# OTP2.net
KiCad netlist of a schematic drawn in Altium Designer
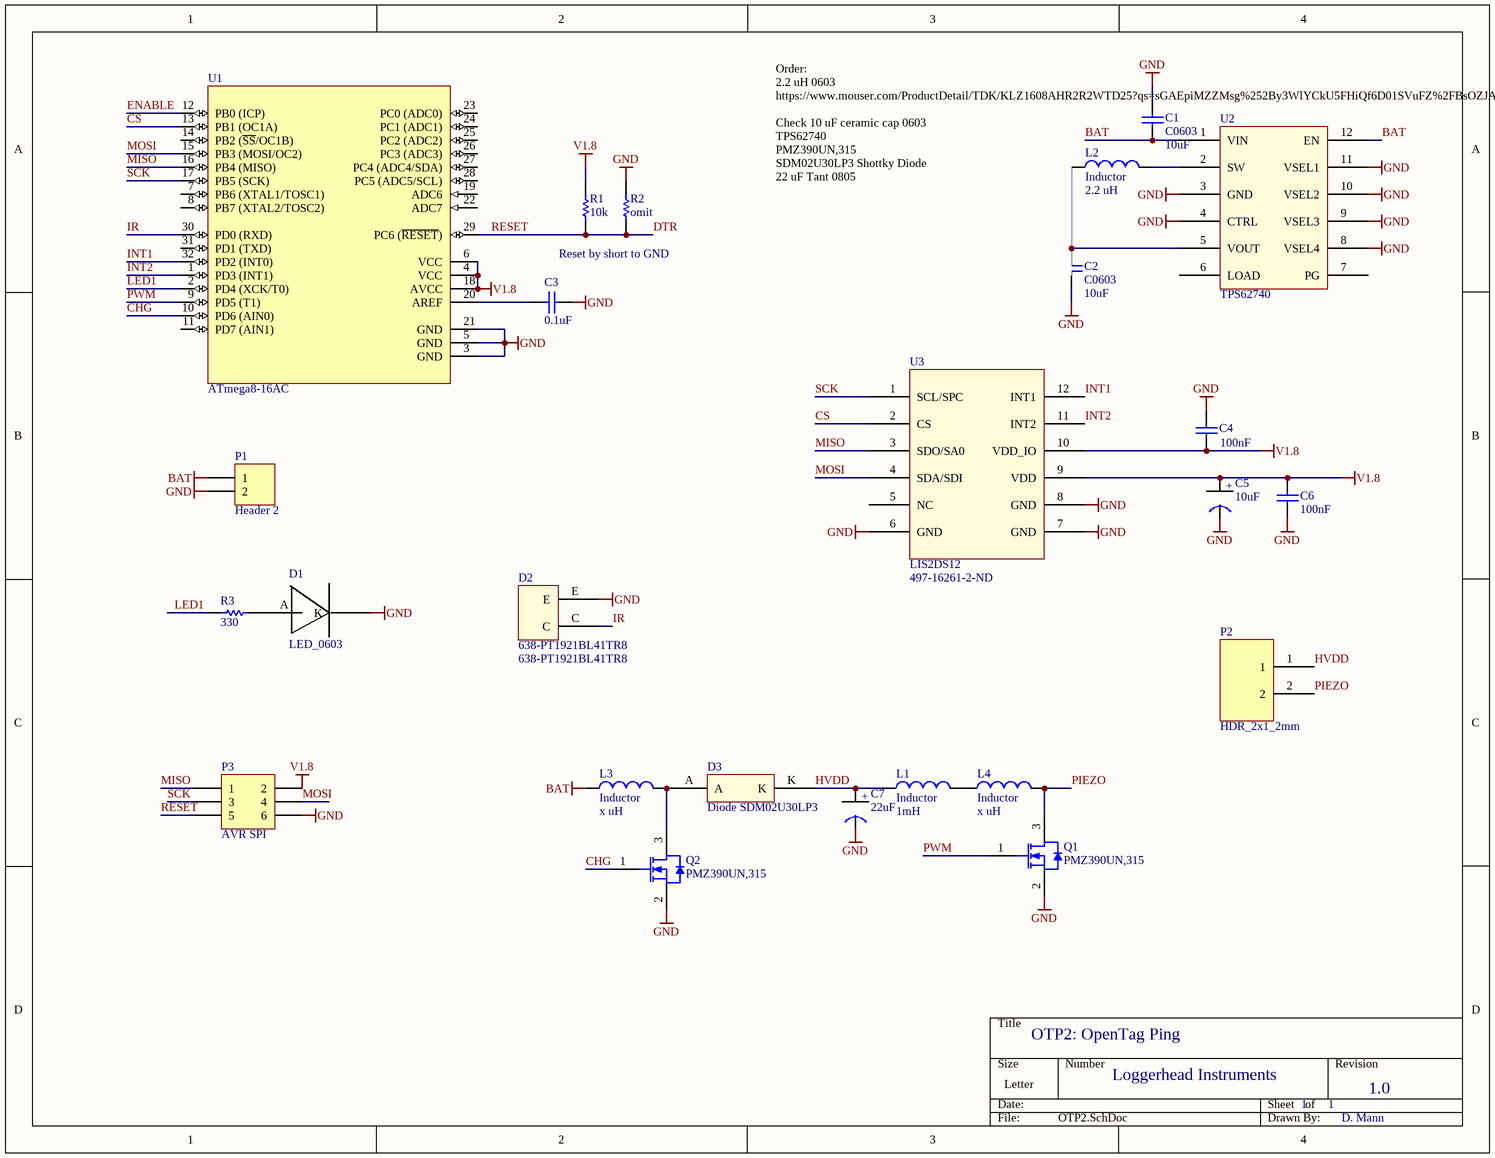
[diagram p0: OTP2.SchDoc]

(export (version "E")
  (design (tool "Eeschema 10.0.6"))
  (components
    (comp (ref "C1")
      (value "C0603")
      (footprint "0603")
      (description "Ceramic Chip Capacitor - Standard")
      (fields (field (name "ALTIUM_VALUE") "10uF") (field (name "PUBLISHER") "Altium Limited"))
      (libsource (lib "KEMET Chip Capacitor") (part "C0603"))
    )
    (comp (ref "C2")
      (value "C0603")
      (footprint "0603")
      (description "Ceramic Chip Capacitor - Standard")
      (fields (field (name "ALTIUM_VALUE") "10uF") (field (name "PUBLISHER") "Altium Limited"))
      (libsource (lib "KEMET Chip Capacitor") (part "C0603"))
    )
    (comp (ref "C3")
      (value "0.1uF")
      (footprint "0402")
      (description "Ceramic Chip Capacitor - Standard")
      (fields (field (name "PUBLISHER") "Altium Limited"))
      (libsource (lib "KEMET Chip Capacitor") (part "C0402"))
    )
    (comp (ref "C4")
      (value "100nF")
      (footprint "0402")
      (description "Ceramic Chip Capacitor - Standard")
      (fields (field (name "PUBLISHER") "Altium Limited"))
      (libsource (lib "KEMET Chip Capacitor") (part "C0402"))
    )
    (comp (ref "C5") (value "10uF") (footprint "Tant0805") (libsource (lib "Loggerhead") (part "Tant0805")))
    (comp (ref "C6")
      (value "100nF")
      (footprint "0402")
      (description "Ceramic Chip Capacitor - Standard")
      (fields (field (name "PUBLISHER") "Altium Limited"))
      (libsource (lib "KEMET Chip Capacitor") (part "C0402"))
    )
    (comp (ref "C7") (value "22uF") (footprint "Tant0805") (libsource (lib "Loggerhead") (part "Tant0805")))
    (comp (ref "D1")
      (value "LED_0603")
      (footprint "Diode0603")
      (libsource (lib "Loggerhead") (part "LED_0603"))
    )
    (comp (ref "D2")
      (value "638-PT1921BL41TR8")
      (footprint "Phototransistor")
      (description "Phototransistor")
      (fields (field (name "SUPPLIER PART NUMBER 1") "638-PT1921BL41TR8"))
      (libsource (lib "Loggerhead") (part "Phototransistor"))
    )
    (comp (ref "D3")
      (value "Diode SDM02U30LP3")
      (footprint "Diode SDM02U30LP3-7B")
      (description "SDM02U30LP3")
      (libsource (lib "Loggerhead") (part "Diode SDM02U30LP3"))
    )
    (comp (ref "L1")
      (value "Inductor")
      (footprint "INDC3216")
      (fields (field (name "ALTIUM_VALUE") "1mH") (field (name "PUBLISHER") "Altium Limited"))
      (libsource (lib "Miscellaneous Devices") (part "Inductor"))
    )
    (comp (ref "L2")
      (value "Inductor")
      (footprint "0603")
      (fields (field (name "ALTIUM_VALUE") "2.2 uH") (field (name "PUBLISHER") "Altium Limited"))
      (libsource (lib "Miscellaneous Devices") (part "Inductor"))
    )
    (comp (ref "L3")
      (value "Inductor")
      (footprint "0603")
      (fields (field (name "ALTIUM_VALUE") "x uH") (field (name "PUBLISHER") "Altium Limited"))
      (libsource (lib "Miscellaneous Devices") (part "Inductor"))
    )
    (comp (ref "L4")
      (value "Inductor")
      (footprint "0603")
      (fields (field (name "ALTIUM_VALUE") "x uH") (field (name "PUBLISHER") "Altium Limited"))
      (libsource (lib "Miscellaneous Devices") (part "Inductor"))
    )
    (comp (ref "P1")
      (value "Header 2")
      (footprint "HDR1X2")
      (description "Header, 2-Pin")
      (fields (field (name "PUBLISHER") "Altium Limited"))
      (libsource (lib "Miscellaneous Connectors") (part "Header 2"))
    )
    (comp (ref "P2")
      (value "HDR_2x1_2mm")
      (footprint "HDR_2x1_2mm")
      (libsource (lib "Loggerhead") (part "HDR_2x1_2mm"))
    )
    (comp (ref "P3")
      (value "AVR SPI")
      (footprint "HDR2X3")
      (description "Header, 3-Pin, Dual row")
      (fields (field (name "PUBLISHER") "Altium Limited"))
      (libsource (lib "Miscellaneous Connectors") (part "Header 3X2"))
    )
    (comp (ref "Q1")
      (value "PMZ390UN,315")
      (footprint "NXP-SOT883_N")
      (description "N-Channel TrenchMOS Standard Level FET, 30 V, 1.78 A, 3-Pin SOT883, Tape and Reel")
      (fields (field (name "MANUFACTURER") "NXP Semiconductors"))
      (libsource (lib "NXP Semiconductors Standard MOSFETs") (part "PMZ390UN,315"))
    )
    (comp (ref "Q2")
      (value "PMZ390UN,315")
      (footprint "NXP-SOT883_N")
      (description "N-Channel TrenchMOS Standard Level FET, 30 V, 1.78 A, 3-Pin SOT883, Tape and Reel")
      (fields (field (name "MANUFACTURER") "NXP Semiconductors"))
      (libsource (lib "NXP Semiconductors Standard MOSFETs") (part "PMZ390UN,315"))
    )
    (comp (ref "R1")
      (value "10k")
      (footprint "3-0603")
      (fields (field (name "PUBLISHER") "Altium Limited"))
      (libsource (lib "Panasonic Resistor") (part "ERJ3RK"))
    )
    (comp (ref "R2")
      (value "omit")
      (footprint "3-0603")
      (fields (field (name "PUBLISHER") "Altium Limited"))
      (libsource (lib "Panasonic Resistor") (part "ERJ3RK"))
    )
    (comp (ref "R3")
      (value "330")
      (footprint "3-0603")
      (fields (field (name "PUBLISHER") "Altium Limited"))
      (libsource (lib "Panasonic Resistor") (part "ERJ3RK"))
    )
    (comp (ref "U1")
      (value "ATmega8-16AC")
      (footprint "32M1-A_M")
      (description "8-Bit AVR Microcontroller with 8K Bytes of In-System Programmable Flash Memory")
      (fields (field (name "PUBLISHER") "Altium Limited"))
      (libsource (lib "Atmel Microcontroller 8-Bit AVR") (part "ATmega8-16AC"))
    )
    (comp (ref "U2")
      (value "TPS62740")
      (footprint "TPS6274x")
      (libsource (lib "Loggerhead") (part "TPS6274x"))
    )
    (comp (ref "U3")
      (value "LIS2DS12")
      (footprint "LGA-12")
      (fields (field (name "SUPPLIER PART NUMBER 1") "497-16261-2-ND"))
      (libsource (lib "Loggerhead") (part "LIS2DS12"))
    )
  )
  (nets
    (net (code "1") (name "/CHG") (class "Default")
      (node (ref "Q2") (pin "1") (pinfunction "G_1") (pintype "passive"))
      (node (ref "U1") (pin "10") (pinfunction "PD6_(AIN0)_10") (pintype "bidirectional"))
    )
    (net (code "2") (name "/CS") (class "Default")
      (node (ref "U1") (pin "13") (pinfunction "PB1_(OC1A)_13") (pintype "bidirectional"))
      (node (ref "U3") (pin "2") (pinfunction "CS_2") (pintype "passive"))
    )
    (net (code "3") (name "/DTR") (class "Default")
      (node (ref "P3") (pin "5") (pinfunction "5_5") (pintype "passive"))
      (node (ref "R1") (pin "1") (pinfunction "1_1") (pintype "passive"))
      (node (ref "R2") (pin "1") (pinfunction "1_1") (pintype "passive"))
      (node (ref "U1") (pin "29") (pinfunction "PC6_(~{RESET})_29") (pintype "bidirectional"))
    )
    (net (code "4") (name "/ENABLE") (class "Default")
      (node (ref "U1") (pin "12") (pinfunction "PB0_(ICP)_12") (pintype "bidirectional"))
    )
    (net (code "5") (name "/HVDD") (class "Default")
      (node (ref "C7") (pin "2") (pinfunction "+_2") (pintype "passive"))
      (node (ref "D3") (pin "K") (pinfunction "K_K") (pintype "passive"))
      (node (ref "L1") (pin "1") (pinfunction "1_1") (pintype "passive"))
      (node (ref "P2") (pin "1") (pinfunction "1_1") (pintype "passive"))
    )
    (net (code "6") (name "/INT1") (class "Default")
      (node (ref "U1") (pin "32") (pinfunction "PD2_(INT0)_32") (pintype "bidirectional"))
      (node (ref "U3") (pin "12") (pinfunction "INT1_12") (pintype "passive"))
    )
    (net (code "7") (name "/INT2") (class "Default")
      (node (ref "U1") (pin "1") (pinfunction "PD3_(INT1)_1") (pintype "bidirectional"))
      (node (ref "U3") (pin "11") (pinfunction "INT2_11") (pintype "passive"))
    )
    (net (code "8") (name "/IR") (class "Default")
      (node (ref "D2") (pin "C") (pinfunction "C_C") (pintype "passive"))
      (node (ref "U1") (pin "30") (pinfunction "PD0_(RXD)_30") (pintype "bidirectional"))
    )
    (net (code "9") (name "/LED1") (class "Default")
      (node (ref "R3") (pin "1") (pinfunction "1_1") (pintype "passive"))
      (node (ref "U1") (pin "2") (pinfunction "PD4_(XCK/T0)_2") (pintype "bidirectional"))
    )
    (net (code "10") (name "/MISO") (class "Default")
      (node (ref "P3") (pin "1") (pinfunction "1_1") (pintype "passive"))
      (node (ref "U1") (pin "16") (pinfunction "PB4_(MISO)_16") (pintype "bidirectional"))
      (node (ref "U3") (pin "3") (pinfunction "SDO/SA0_3") (pintype "passive"))
    )
    (net (code "11") (name "/MOSI") (class "Default")
      (node (ref "P3") (pin "4") (pinfunction "4_4") (pintype "passive"))
      (node (ref "U1") (pin "15") (pinfunction "PB3_(MOSI/OC2)_15") (pintype "bidirectional"))
      (node (ref "U3") (pin "4") (pinfunction "SDA/SDI_4") (pintype "passive"))
    )
    (net (code "12") (name "/PIEZO") (class "Default")
      (node (ref "L4") (pin "2") (pinfunction "2_2") (pintype "passive"))
      (node (ref "P2") (pin "2") (pinfunction "2_2") (pintype "passive"))
      (node (ref "Q1") (pin "3") (pinfunction "D_3") (pintype "passive"))
    )
    (net (code "13") (name "/PWM") (class "Default")
      (node (ref "Q1") (pin "1") (pinfunction "G_1") (pintype "passive"))
      (node (ref "U1") (pin "9") (pinfunction "PD5_(T1)_9") (pintype "bidirectional"))
    )
    (net (code "14") (name "/SCK") (class "Default")
      (node (ref "P3") (pin "3") (pinfunction "3_3") (pintype "passive"))
      (node (ref "U1") (pin "17") (pinfunction "PB5_(SCK)_17") (pintype "bidirectional"))
      (node (ref "U3") (pin "1") (pinfunction "SCL/SPC_1") (pintype "passive"))
    )
    (net (code "15") (name "BAT") (class "Default")
      (node (ref "C1") (pin "1") (pinfunction "1_1") (pintype "passive"))
      (node (ref "L3") (pin "1") (pinfunction "1_1") (pintype "passive"))
      (node (ref "P1") (pin "1") (pinfunction "1_1") (pintype "passive"))
      (node (ref "U2") (pin "1") (pinfunction "VIN_1") (pintype "passive"))
      (node (ref "U2") (pin "12") (pinfunction "EN_12") (pintype "passive"))
    )
    (net (code "16") (name "GND") (class "Default")
      (node (ref "C1") (pin "2") (pinfunction "2_2") (pintype "passive"))
      (node (ref "C2") (pin "1") (pinfunction "1_1") (pintype "passive"))
      (node (ref "C3") (pin "2") (pinfunction "2_2") (pintype "passive"))
      (node (ref "C4") (pin "2") (pinfunction "2_2") (pintype "passive"))
      (node (ref "C5") (pin "1") (pinfunction "GND_1") (pintype "passive"))
      (node (ref "C6") (pin "2") (pinfunction "2_2") (pintype "passive"))
      (node (ref "C7") (pin "1") (pinfunction "GND_1") (pintype "passive"))
      (node (ref "D1") (pin "K") (pinfunction "K_K") (pintype "passive"))
      (node (ref "D2") (pin "E") (pinfunction "E_E") (pintype "passive"))
      (node (ref "P1") (pin "2") (pinfunction "2_2") (pintype "passive"))
      (node (ref "P3") (pin "6") (pinfunction "6_6") (pintype "passive"))
      (node (ref "Q1") (pin "2") (pinfunction "S_2") (pintype "passive"))
      (node (ref "Q2") (pin "2") (pinfunction "S_2") (pintype "passive"))
      (node (ref "R2") (pin "2") (pinfunction "2_2") (pintype "passive"))
      (node (ref "U1") (pin "21") (pinfunction "GND_21") (pintype "power_in"))
      (node (ref "U1") (pin "3") (pinfunction "GND_3") (pintype "power_in"))
      (node (ref "U1") (pin "5") (pinfunction "GND_5") (pintype "power_in"))
      (node (ref "U2") (pin "10") (pinfunction "VSEL2_10") (pintype "passive"))
      (node (ref "U2") (pin "11") (pinfunction "VSEL1_11") (pintype "passive"))
      (node (ref "U2") (pin "3") (pinfunction "GND_3") (pintype "passive"))
      (node (ref "U2") (pin "4") (pinfunction "CTRL_4") (pintype "passive"))
      (node (ref "U2") (pin "8") (pinfunction "VSEL4_8") (pintype "passive"))
      (node (ref "U2") (pin "9") (pinfunction "VSEL3_9") (pintype "passive"))
      (node (ref "U3") (pin "6") (pinfunction "GND_6") (pintype "passive"))
      (node (ref "U3") (pin "7") (pinfunction "GND_7") (pintype "passive"))
      (node (ref "U3") (pin "8") (pinfunction "GND_8") (pintype "passive"))
    )
    (net (code "17") (name "Net-(D1-PadA)") (class "Default")
      (node (ref "D1") (pin "A") (pinfunction "A_A") (pintype "passive"))
      (node (ref "R3") (pin "2") (pinfunction "2_2") (pintype "passive"))
    )
    (net (code "18") (name "Net-(L1-Pad2)") (class "Default")
      (node (ref "L1") (pin "2") (pinfunction "2_2") (pintype "passive"))
      (node (ref "L4") (pin "1") (pinfunction "1_1") (pintype "passive"))
    )
    (net (code "19") (name "Net-(Q2-D)") (class "Default")
      (node (ref "D3") (pin "A") (pinfunction "A_A") (pintype "passive"))
      (node (ref "L3") (pin "2") (pinfunction "2_2") (pintype "passive"))
      (node (ref "Q2") (pin "3") (pinfunction "D_3") (pintype "passive"))
    )
    (net (code "20") (name "Net-(U1-AREF)") (class "Default")
      (node (ref "C3") (pin "1") (pinfunction "1_1") (pintype "passive"))
      (node (ref "U1") (pin "20") (pinfunction "AREF_20") (pintype "passive"))
    )
    (net (code "21") (name "Net-(U2-SW)") (class "Default")
      (node (ref "L2") (pin "2") (pinfunction "2_2") (pintype "passive"))
      (node (ref "U2") (pin "2") (pinfunction "SW_2") (pintype "passive"))
    )
    (net (code "22") (name "V1.8") (class "Default")
      (node (ref "C2") (pin "2") (pinfunction "2_2") (pintype "passive"))
      (node (ref "C4") (pin "1") (pinfunction "1_1") (pintype "passive"))
      (node (ref "C5") (pin "2") (pinfunction "+_2") (pintype "passive"))
      (node (ref "C6") (pin "1") (pinfunction "1_1") (pintype "passive"))
      (node (ref "L2") (pin "1") (pinfunction "1_1") (pintype "passive"))
      (node (ref "P3") (pin "2") (pinfunction "2_2") (pintype "passive"))
      (node (ref "R1") (pin "2") (pinfunction "2_2") (pintype "passive"))
      (node (ref "U1") (pin "18") (pinfunction "AVCC_18") (pintype "power_in"))
      (node (ref "U1") (pin "4") (pinfunction "VCC_4") (pintype "power_in"))
      (node (ref "U1") (pin "6") (pinfunction "VCC_6") (pintype "power_in"))
      (node (ref "U2") (pin "5") (pinfunction "VOUT_5") (pintype "passive"))
      (node (ref "U3") (pin "10") (pinfunction "VDD_IO_10") (pintype "passive"))
      (node (ref "U3") (pin "9") (pinfunction "VDD_9") (pintype "passive"))
    )
    (net (code "23") (name "unconnected-(U1-ADC6-Pad19)") (class "Default")
      (node (ref "U1") (pin "19") (pinfunction "ADC6_19") (pintype "input"))
    )
    (net (code "24") (name "unconnected-(U1-ADC7-Pad22)") (class "Default")
      (node (ref "U1") (pin "22") (pinfunction "ADC7_22") (pintype "input"))
    )
    (net (code "25") (name "unconnected-(U1-PB2_(~{SS}{slash}OC1B)-Pad14)") (class "Default")
      (node (ref "U1") (pin "14") (pinfunction "PB2_(~{SS}/OC1B)_14") (pintype "bidirectional"))
    )
    (net (code "26") (name "unconnected-(U1-PB6_(XTAL1{slash}TOSC1)-Pad7)") (class "Default")
      (node (ref "U1") (pin "7") (pinfunction "PB6_(XTAL1/TOSC1)_7") (pintype "bidirectional"))
    )
    (net (code "27") (name "unconnected-(U1-PB7_(XTAL2{slash}TOSC2)-Pad8)") (class "Default")
      (node (ref "U1") (pin "8") (pinfunction "PB7_(XTAL2/TOSC2)_8") (pintype "bidirectional"))
    )
    (net (code "28") (name "unconnected-(U1-PC0_(ADC0)-Pad23)") (class "Default")
      (node (ref "U1") (pin "23") (pinfunction "PC0_(ADC0)_23") (pintype "bidirectional"))
    )
    (net (code "29") (name "unconnected-(U1-PC1_(ADC1)-Pad24)") (class "Default")
      (node (ref "U1") (pin "24") (pinfunction "PC1_(ADC1)_24") (pintype "bidirectional"))
    )
    (net (code "30") (name "unconnected-(U1-PC2_(ADC2)-Pad25)") (class "Default")
      (node (ref "U1") (pin "25") (pinfunction "PC2_(ADC2)_25") (pintype "bidirectional"))
    )
    (net (code "31") (name "unconnected-(U1-PC3_(ADC3)-Pad26)") (class "Default")
      (node (ref "U1") (pin "26") (pinfunction "PC3_(ADC3)_26") (pintype "bidirectional"))
    )
    (net (code "32") (name "unconnected-(U1-PC4_(ADC4{slash}SDA)-Pad27)") (class "Default")
      (node (ref "U1") (pin "27") (pinfunction "PC4_(ADC4/SDA)_27") (pintype "bidirectional"))
    )
    (net (code "33") (name "unconnected-(U1-PC5_(ADC5{slash}SCL)-Pad28)") (class "Default")
      (node (ref "U1") (pin "28") (pinfunction "PC5_(ADC5/SCL)_28") (pintype "bidirectional"))
    )
    (net (code "34") (name "unconnected-(U1-PD1_(TXD)-Pad31)") (class "Default")
      (node (ref "U1") (pin "31") (pinfunction "PD1_(TXD)_31") (pintype "bidirectional"))
    )
    (net (code "35") (name "unconnected-(U1-PD7_(AIN1)-Pad11)") (class "Default")
      (node (ref "U1") (pin "11") (pinfunction "PD7_(AIN1)_11") (pintype "bidirectional"))
    )
    (net (code "36") (name "unconnected-(U2-LOAD-Pad6)") (class "Default")
      (node (ref "U2") (pin "6") (pinfunction "LOAD_6") (pintype "passive"))
    )
    (net (code "37") (name "unconnected-(U2-PG-Pad7)") (class "Default")
      (node (ref "U2") (pin "7") (pinfunction "PG_7") (pintype "passive"))
    )
    (net (code "38") (name "unconnected-(U3-NC-Pad5)") (class "Default")
      (node (ref "U3") (pin "5") (pinfunction "NC_5") (pintype "passive"))
    )
  )
)
